# EasyEDA.net
KiCad netlist of a schematic drawn in EasyEDA Pro
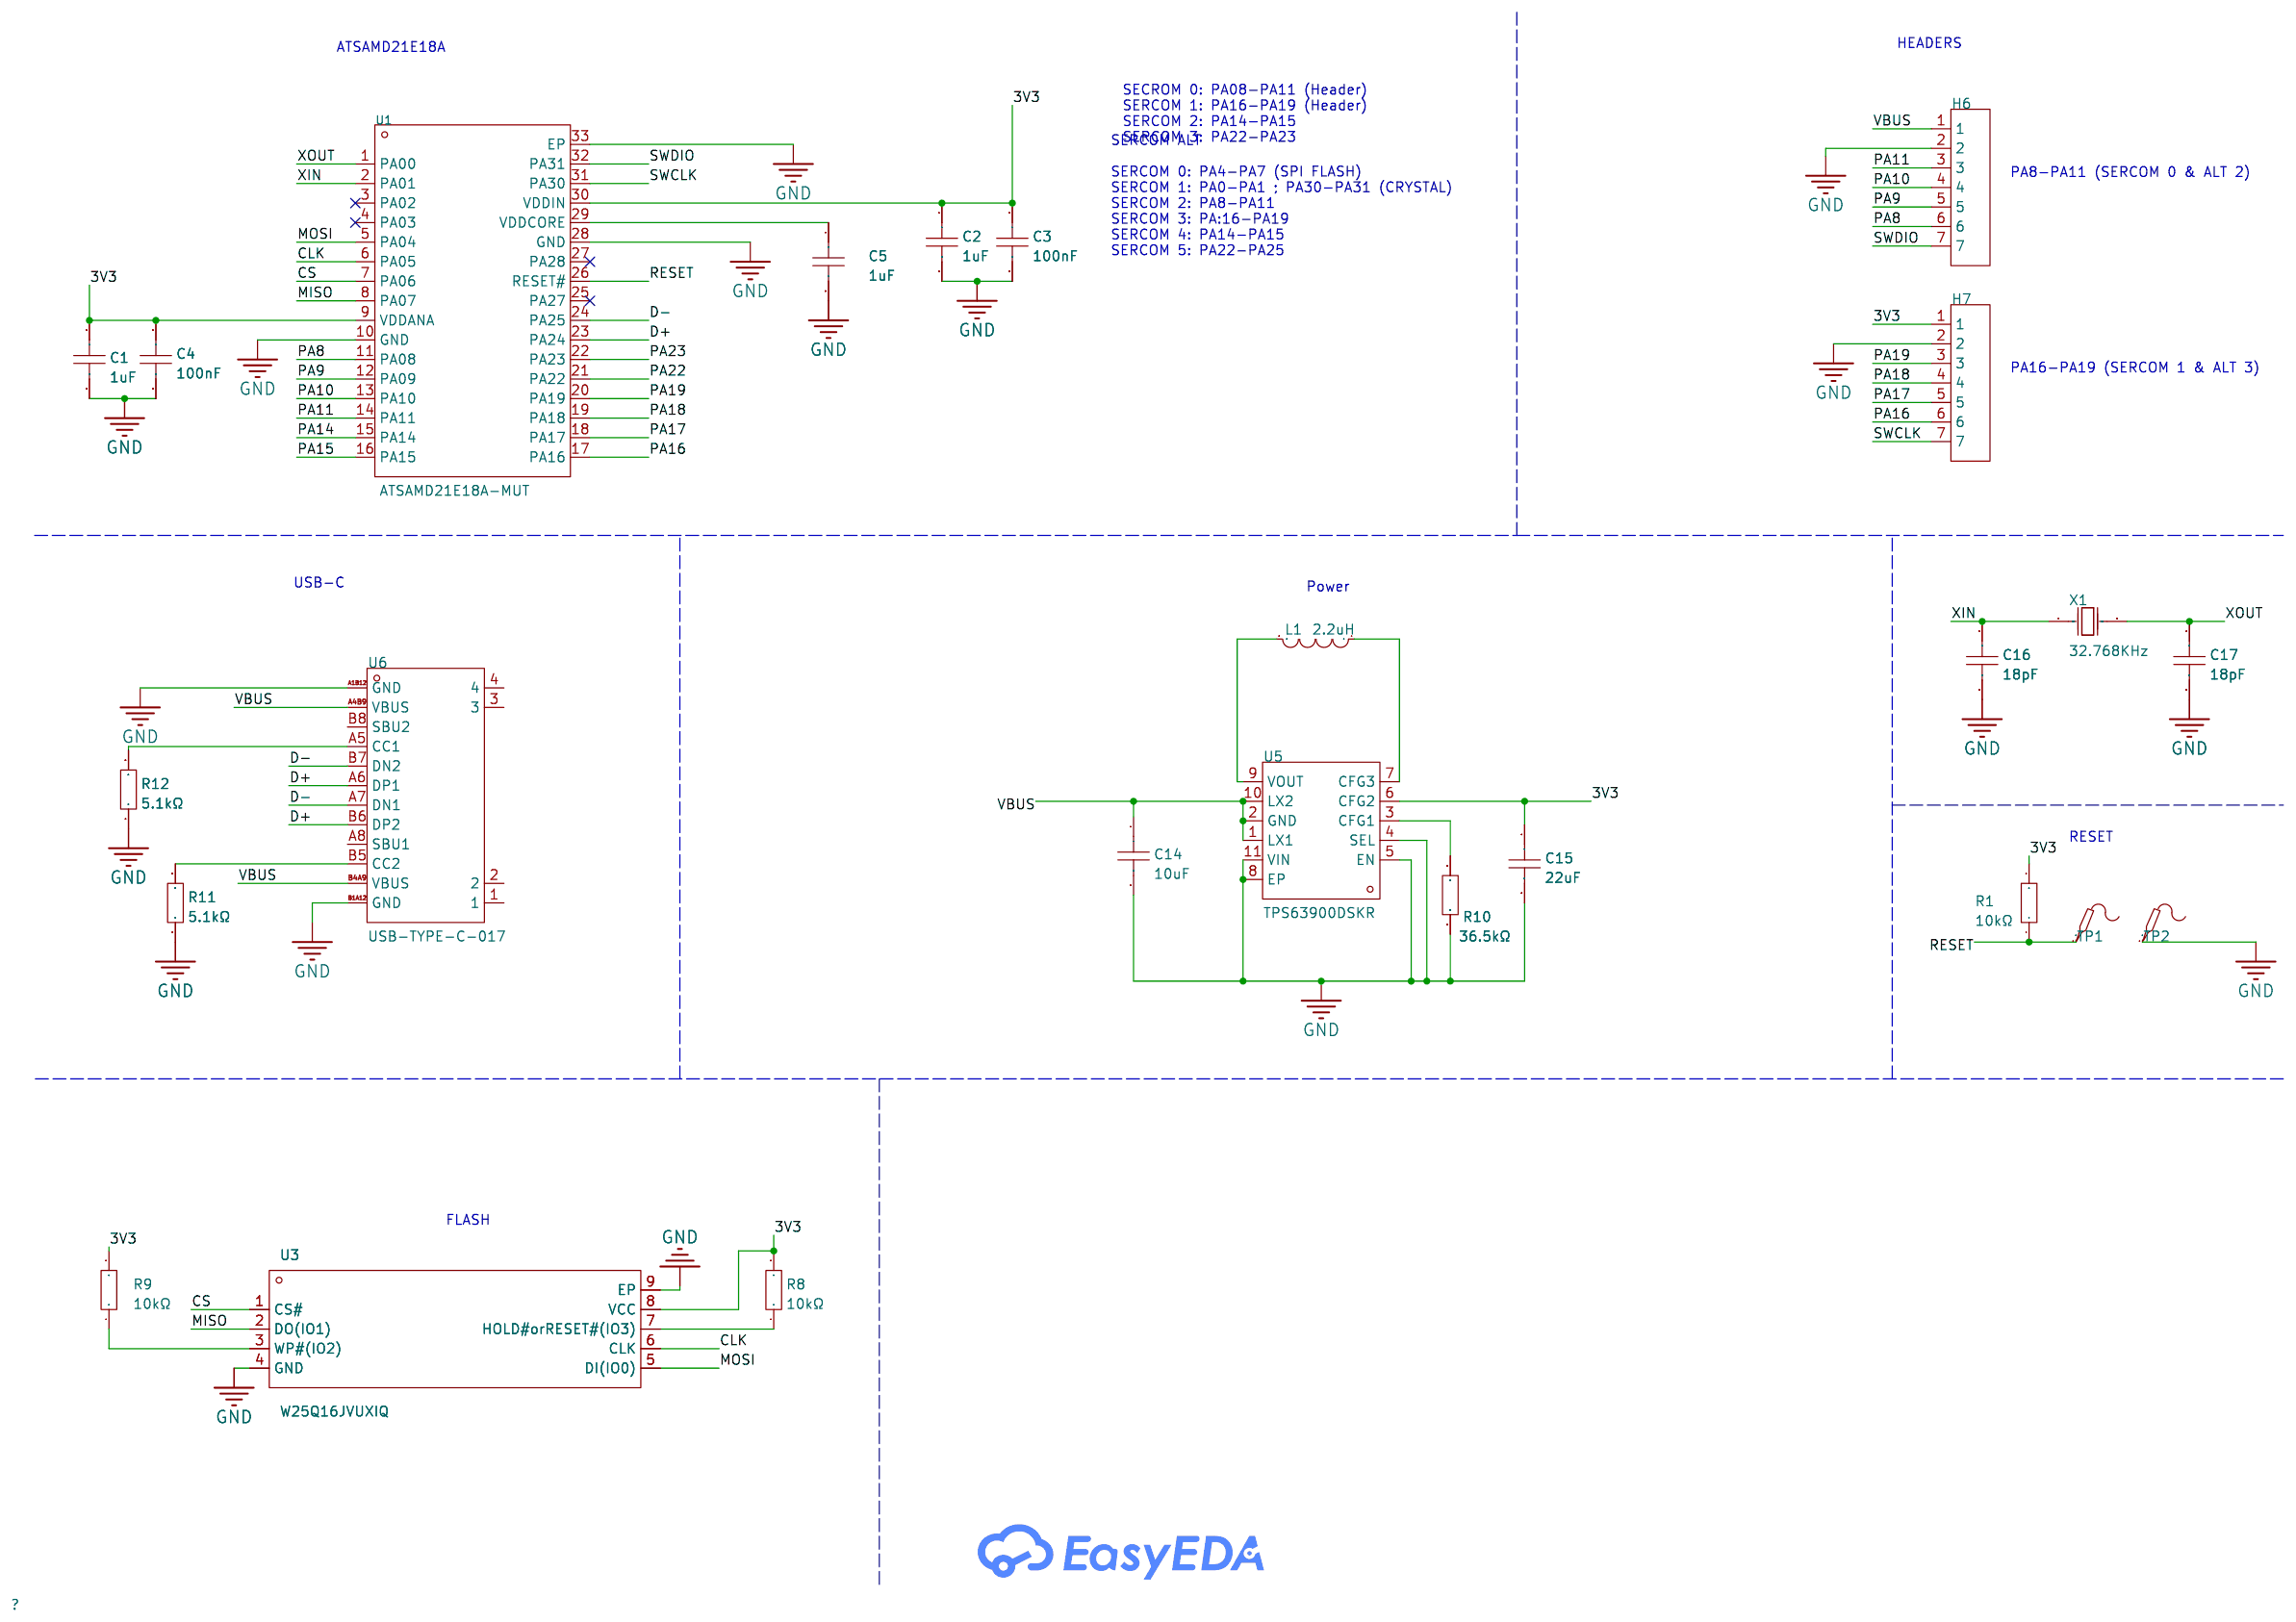
[diagram p0: schematic sheet]

(export (version "E")
  (design (tool "Eeschema 10.0.6"))
  (components
    (comp (ref "C1")
      (value "1uF")
      (footprint "easyedapro:C0402")
      (fields
        (field (name "Manufacturer Part") "CL05A105KA5NQNC")
        (field (name "Manufacturer") "SAMSUNG(三星)")
      )
      (libsource (lib "easyedapro") (part "CAP"))
    )
    (comp (ref "C2")
      (value "1uF")
      (footprint "easyedapro:C0402")
      (fields
        (field (name "Manufacturer Part") "CL05A105KA5NQNC")
        (field (name "Manufacturer") "SAMSUNG(三星)")
      )
      (libsource (lib "easyedapro") (part "CAP"))
    )
    (comp (ref "C3")
      (value "100nF")
      (footprint "easyedapro:C0402")
      (fields
        (field (name "Manufacturer Part") "CL05B104KO5NNNC")
        (field (name "Manufacturer") "SAMSUNG(三星)")
      )
      (libsource (lib "easyedapro") (part "CAP"))
    )
    (comp (ref "C4")
      (value "100nF")
      (footprint "easyedapro:C0402")
      (fields
        (field (name "Manufacturer Part") "CL05B104KO5NNNC")
        (field (name "Manufacturer") "SAMSUNG(三星)")
      )
      (libsource (lib "easyedapro") (part "CAP"))
    )
    (comp (ref "C5")
      (value "1uF")
      (footprint "easyedapro:C0402")
      (fields
        (field (name "Manufacturer Part") "CL05A105KA5NQNC")
        (field (name "Manufacturer") "SAMSUNG(三星)")
      )
      (libsource (lib "easyedapro") (part "CAP"))
    )
    (comp (ref "C14")
      (value "10uF")
      (footprint "easyedapro:C0402")
      (fields
        (field (name "Manufacturer Part") "CL05A106MQ5NUNC")
        (field (name "Manufacturer") "SAMSUNG(三星)")
      )
      (libsource (lib "easyedapro") (part "CAP"))
    )
    (comp (ref "C15")
      (value "22uF")
      (footprint "easyedapro:C0402")
      (fields
        (field (name "Manufacturer Part") "CL21A226MAQNNNE")
        (field (name "Manufacturer") "SAMSUNG(三星)")
      )
      (libsource (lib "easyedapro") (part "CAP"))
    )
    (comp (ref "C16")
      (value "18pF")
      (footprint "easyedapro:C0402")
      (libsource (lib "easyedapro") (part "CAP"))
    )
    (comp (ref "C17")
      (value "18pF")
      (footprint "easyedapro:C0402")
      (libsource (lib "easyedapro") (part "CAP"))
    )
    (comp (ref "H6")
      (value "~")
      (footprint "easyedapro:HDR-TH_7P-P2.54-V-M")
      (libsource (lib "easyedapro") (part "PZ254V-11-07P"))
    )
    (comp (ref "H7")
      (value "~")
      (footprint "easyedapro:HDR-TH_7P-P2.54-V-M")
      (libsource (lib "easyedapro") (part "PZ254V-11-07P"))
    )
    (comp (ref "L1")
      (value "2.2uH")
      (footprint "easyedapro:L0402")
      (fields (field (name "Manufacturer Part") "CY43-2.2UH") (field (name "Manufacturer") "SHOU HAN(首韩)"))
      (libsource (lib "easyedapro") (part "电感"))
    )
    (comp (ref "R1")
      (value "10kΩ")
      (footprint "easyedapro:R0603")
      (fields
        (field (name "Manufacturer Part") "0402WGF1002TCE")
        (field (name "Manufacturer") "UNI-ROYAL(厚声)")
      )
      (libsource (lib "easyedapro") (part "Res"))
    )
    (comp (ref "R8")
      (value "10kΩ")
      (footprint "easyedapro:R0603")
      (fields
        (field (name "Manufacturer Part") "0402WGF1002TCE")
        (field (name "Manufacturer") "UNI-ROYAL(厚声)")
      )
      (libsource (lib "easyedapro") (part "Res"))
    )
    (comp (ref "R9")
      (value "10kΩ")
      (footprint "easyedapro:R0603")
      (fields
        (field (name "Manufacturer Part") "0402WGF1002TCE")
        (field (name "Manufacturer") "UNI-ROYAL(厚声)")
      )
      (libsource (lib "easyedapro") (part "Res"))
    )
    (comp (ref "R10")
      (value "36.5kΩ")
      (footprint "easyedapro:R0603")
      (fields (field (name "Manufacturer Part") "AC0402FR-0736K5L") (field (name "Manufacturer") "YAGEO(国巨)"))
      (libsource (lib "easyedapro") (part "Res"))
    )
    (comp (ref "R11")
      (value "5.1kΩ")
      (footprint "easyedapro:R0603")
      (fields
        (field (name "Manufacturer Part") "0402WGF5101TCE")
        (field (name "Manufacturer") "UNI-ROYAL(厚声)")
      )
      (libsource (lib "easyedapro") (part "Res"))
    )
    (comp (ref "R12")
      (value "5.1kΩ")
      (footprint "easyedapro:R0603")
      (fields
        (field (name "Manufacturer Part") "0402WGF5101TCE")
        (field (name "Manufacturer") "UNI-ROYAL(厚声)")
      )
      (libsource (lib "easyedapro") (part "Res"))
    )
    (comp (ref "TP1")
      (value "~")
      (footprint "easyedapro:Test-Point-0.5mm")
      (description "Test Point 测试点")
      (libsource (lib "easyedapro") (part "Test-Point"))
    )
    (comp (ref "TP2")
      (value "~")
      (footprint "easyedapro:Test-Point-0.5mm")
      (description "Test Point 测试点")
      (libsource (lib "easyedapro") (part "Test-Point"))
    )
    (comp (ref "U1")
      (value "ATSAMD21E18A-MUT")
      (footprint "easyedapro:QFN-32_L5.0-W5.0-P0.50-TL-EP3.6")
      (fields (field (name "Manufacturer") "MICROCHIP(美国微芯)"))
      (libsource (lib "easyedapro") (part "ATSAMD21E18A-MUT_C2052801"))
    )
    (comp (ref "U3")
      (value "W25Q16JVUXIQ")
      (footprint "easyedapro:USON-8_L3.0-W2.0-P0.50-BL-EP")
      (fields (field (name "Manufacturer") "WINBOND(华邦)"))
      (libsource (lib "easyedapro") (part "W25Q16JVUXIQ"))
    )
    (comp (ref "U5")
      (value "TPS63900DSKR")
      (footprint "easyedapro:WSON-10_L2.5-W2.5-W0.50-TL-EP")
      (fields (field (name "Manufacturer") "TI(德州仪器)"))
      (libsource (lib "easyedapro") (part "TPS63900DSKR"))
    )
    (comp (ref "U6")
      (value "USB-TYPE-C-017")
      (footprint "easyedapro:USB-TYPE-C-SMD_C9900008089")
      (fields (field (name "Manufacturer") "DEALON(德艺隆)"))
      (libsource (lib "easyedapro") (part "USB-TYPE-C-017"))
    )
    (comp (ref "X1")
      (value "32.768KHz")
      (footprint "easyedapro:OSC-SMD_L3.2-W1.5")
      (fields (field (name "Manufacturer Part") "FC-135R") (field (name "Manufacturer") "EPSON"))
      (libsource (lib "easyedapro") (part "32.768KHz"))
    )
  )
  (nets
    (net (code "1") (name "/3V3") (class "Default")
      (node (ref "C1") (pin "1") (pinfunction "1_1") (pintype "input"))
      (node (ref "C15") (pin "1") (pinfunction "1_1") (pintype "input"))
      (node (ref "C2") (pin "1") (pinfunction "1_1") (pintype "input"))
      (node (ref "C3") (pin "1") (pinfunction "1_1") (pintype "input"))
      (node (ref "C4") (pin "1") (pinfunction "1_1") (pintype "input"))
      (node (ref "H7") (pin "1") (pinfunction "1_1") (pintype "unspecified"))
      (node (ref "R1") (pin "2") (pinfunction "2_2") (pintype "input"))
      (node (ref "R8") (pin "2") (pinfunction "2_2") (pintype "input"))
      (node (ref "R9") (pin "2") (pinfunction "2_2") (pintype "input"))
      (node (ref "U1") (pin "30") (pinfunction "VDDIN_30") (pintype "input"))
      (node (ref "U1") (pin "9") (pinfunction "VDDANA_9") (pintype "input"))
      (node (ref "U3") (pin "8") (pinfunction "VCC_8") (pintype "unspecified"))
      (node (ref "U5") (pin "6") (pinfunction "CFG2_6") (pintype "unspecified"))
    )
    (net (code "2") (name "/CLK") (class "Default")
      (node (ref "U1") (pin "6") (pinfunction "PA05_6") (pintype "input"))
      (node (ref "U3") (pin "6") (pinfunction "CLK_6") (pintype "unspecified"))
    )
    (net (code "3") (name "/CS") (class "Default")
      (node (ref "U1") (pin "7") (pinfunction "PA06_7") (pintype "input"))
      (node (ref "U3") (pin "1") (pinfunction "CS#_1") (pintype "unspecified"))
    )
    (net (code "4") (name "/D+") (class "Default")
      (node (ref "U1") (pin "23") (pinfunction "PA24_23") (pintype "input"))
      (node (ref "U6") (pin "A6") (pinfunction "DP1_A6") (pintype "unspecified"))
      (node (ref "U6") (pin "B6") (pinfunction "DP2_B6") (pintype "unspecified"))
    )
    (net (code "5") (name "/D-") (class "Default")
      (node (ref "U1") (pin "24") (pinfunction "PA25_24") (pintype "input"))
      (node (ref "U6") (pin "A7") (pinfunction "DN1_A7") (pintype "unspecified"))
      (node (ref "U6") (pin "B7") (pinfunction "DN2_B7") (pintype "unspecified"))
    )
    (net (code "6") (name "/MISO") (class "Default")
      (node (ref "U1") (pin "8") (pinfunction "PA07_8") (pintype "input"))
      (node (ref "U3") (pin "2") (pinfunction "DO(IO1)_2") (pintype "unspecified"))
    )
    (net (code "7") (name "/MOSI") (class "Default")
      (node (ref "U1") (pin "5") (pinfunction "PA04_5") (pintype "input"))
      (node (ref "U3") (pin "5") (pinfunction "DI(IO0)_5") (pintype "unspecified"))
    )
    (net (code "8") (name "/PA8") (class "Default")
      (node (ref "H6") (pin "6") (pinfunction "6_6") (pintype "unspecified"))
      (node (ref "U1") (pin "11") (pinfunction "PA08_11") (pintype "input"))
    )
    (net (code "9") (name "/PA9") (class "Default")
      (node (ref "H6") (pin "5") (pinfunction "5_5") (pintype "unspecified"))
      (node (ref "U1") (pin "12") (pinfunction "PA09_12") (pintype "input"))
    )
    (net (code "10") (name "/PA10") (class "Default")
      (node (ref "H6") (pin "4") (pinfunction "4_4") (pintype "unspecified"))
      (node (ref "U1") (pin "13") (pinfunction "PA10_13") (pintype "input"))
    )
    (net (code "11") (name "/PA11") (class "Default")
      (node (ref "H6") (pin "3") (pinfunction "3_3") (pintype "unspecified"))
      (node (ref "U1") (pin "14") (pinfunction "PA11_14") (pintype "input"))
    )
    (net (code "12") (name "/PA14") (class "Default")
      (node (ref "U1") (pin "15") (pinfunction "PA14_15") (pintype "input"))
    )
    (net (code "13") (name "/PA15") (class "Default")
      (node (ref "U1") (pin "16") (pinfunction "PA15_16") (pintype "input"))
    )
    (net (code "14") (name "/PA16") (class "Default")
      (node (ref "H7") (pin "6") (pinfunction "6_6") (pintype "unspecified"))
      (node (ref "U1") (pin "17") (pinfunction "PA16_17") (pintype "input"))
    )
    (net (code "15") (name "/PA17") (class "Default")
      (node (ref "H7") (pin "5") (pinfunction "5_5") (pintype "unspecified"))
      (node (ref "U1") (pin "18") (pinfunction "PA17_18") (pintype "input"))
    )
    (net (code "16") (name "/PA18") (class "Default")
      (node (ref "H7") (pin "4") (pinfunction "4_4") (pintype "unspecified"))
      (node (ref "U1") (pin "19") (pinfunction "PA18_19") (pintype "input"))
    )
    (net (code "17") (name "/PA19") (class "Default")
      (node (ref "H7") (pin "3") (pinfunction "3_3") (pintype "unspecified"))
      (node (ref "U1") (pin "20") (pinfunction "PA19_20") (pintype "input"))
    )
    (net (code "18") (name "/PA22") (class "Default")
      (node (ref "U1") (pin "21") (pinfunction "PA22_21") (pintype "input"))
    )
    (net (code "19") (name "/PA23") (class "Default")
      (node (ref "U1") (pin "22") (pinfunction "PA23_22") (pintype "input"))
    )
    (net (code "20") (name "/RESET") (class "Default")
      (node (ref "R1") (pin "1") (pinfunction "1_1") (pintype "input"))
      (node (ref "TP1") (pin "1") (pinfunction "1_1") (pintype "unspecified"))
      (node (ref "U1") (pin "26") (pinfunction "RESET#_26") (pintype "input"))
    )
    (net (code "21") (name "/SWCLK") (class "Default")
      (node (ref "H7") (pin "7") (pinfunction "7_7") (pintype "unspecified"))
      (node (ref "U1") (pin "31") (pinfunction "PA30_31") (pintype "input"))
    )
    (net (code "22") (name "/SWDIO") (class "Default")
      (node (ref "H6") (pin "7") (pinfunction "7_7") (pintype "unspecified"))
      (node (ref "U1") (pin "32") (pinfunction "PA31_32") (pintype "input"))
    )
    (net (code "23") (name "/VBUS") (class "Default")
      (node (ref "C14") (pin "1") (pinfunction "1_1") (pintype "input"))
      (node (ref "H6") (pin "1") (pinfunction "1_1") (pintype "unspecified"))
      (node (ref "U5") (pin "1") (pinfunction "LX1_1") (pintype "unspecified"))
      (node (ref "U5") (pin "10") (pinfunction "LX2_10") (pintype "unspecified"))
      (node (ref "U5") (pin "2") (pinfunction "GND_2") (pintype "unspecified"))
      (node (ref "U6") (pin "A4B9") (pinfunction "VBUS_A4B9") (pintype "unspecified"))
      (node (ref "U6") (pin "B4A9") (pinfunction "VBUS_B4A9") (pintype "unspecified"))
    )
    (net (code "24") (name "/XIN") (class "Default")
      (node (ref "C16") (pin "1") (pinfunction "1_1") (pintype "input"))
      (node (ref "U1") (pin "2") (pinfunction "PA01_2") (pintype "input"))
      (node (ref "X1") (pin "1") (pinfunction "OSC1_1") (pintype "input"))
    )
    (net (code "25") (name "/XOUT") (class "Default")
      (node (ref "C17") (pin "1") (pinfunction "1_1") (pintype "input"))
      (node (ref "U1") (pin "1") (pinfunction "PA00_1") (pintype "input"))
      (node (ref "X1") (pin "2") (pinfunction "OSC2_2") (pintype "input"))
    )
    (net (code "26") (name "GND") (class "Default")
      (node (ref "C1") (pin "2") (pinfunction "2_2") (pintype "input"))
      (node (ref "C14") (pin "2") (pinfunction "2_2") (pintype "input"))
      (node (ref "C15") (pin "2") (pinfunction "2_2") (pintype "input"))
      (node (ref "C16") (pin "2") (pinfunction "2_2") (pintype "input"))
      (node (ref "C17") (pin "2") (pinfunction "2_2") (pintype "input"))
      (node (ref "C2") (pin "2") (pinfunction "2_2") (pintype "input"))
      (node (ref "C3") (pin "2") (pinfunction "2_2") (pintype "input"))
      (node (ref "C4") (pin "2") (pinfunction "2_2") (pintype "input"))
      (node (ref "C5") (pin "2") (pinfunction "2_2") (pintype "input"))
      (node (ref "H6") (pin "2") (pinfunction "2_2") (pintype "unspecified"))
      (node (ref "H7") (pin "2") (pinfunction "2_2") (pintype "unspecified"))
      (node (ref "R10") (pin "2") (pinfunction "2_2") (pintype "input"))
      (node (ref "R11") (pin "1") (pinfunction "1_1") (pintype "input"))
      (node (ref "R12") (pin "1") (pinfunction "1_1") (pintype "input"))
      (node (ref "TP2") (pin "1") (pinfunction "1_1") (pintype "unspecified"))
      (node (ref "U1") (pin "10") (pinfunction "GND_10") (pintype "input"))
      (node (ref "U1") (pin "28") (pinfunction "GND_28") (pintype "input"))
      (node (ref "U1") (pin "33") (pinfunction "EP_33") (pintype "input"))
      (node (ref "U3") (pin "4") (pinfunction "GND_4") (pintype "unspecified"))
      (node (ref "U3") (pin "9") (pinfunction "EP_9") (pintype "unspecified"))
      (node (ref "U5") (pin "11") (pinfunction "VIN_11") (pintype "unspecified"))
      (node (ref "U5") (pin "4") (pinfunction "SEL_4") (pintype "unspecified"))
      (node (ref "U5") (pin "5") (pinfunction "EN_5") (pintype "unspecified"))
      (node (ref "U5") (pin "8") (pinfunction "EP_8") (pintype "unspecified"))
      (node (ref "U6") (pin "A1B12") (pinfunction "GND_A1B12") (pintype "unspecified"))
      (node (ref "U6") (pin "B1A12") (pinfunction "GND_B1A12") (pintype "unspecified"))
    )
    (net (code "27") (name "Net-(U1-VDDCORE)") (class "Default")
      (node (ref "C5") (pin "1") (pinfunction "1_1") (pintype "input"))
      (node (ref "U1") (pin "29") (pinfunction "VDDCORE_29") (pintype "input"))
    )
    (net (code "28") (name "Net-(U3-HOLD#orRESET#(IO3))") (class "Default")
      (node (ref "R8") (pin "1") (pinfunction "1_1") (pintype "input"))
      (node (ref "U3") (pin "7") (pinfunction "HOLD#orRESET#(IO3)_7") (pintype "unspecified"))
    )
    (net (code "29") (name "Net-(U3-WP#(IO2))") (class "Default")
      (node (ref "R9") (pin "1") (pinfunction "1_1") (pintype "input"))
      (node (ref "U3") (pin "3") (pinfunction "WP#(IO2)_3") (pintype "unspecified"))
    )
    (net (code "30") (name "Net-(U5-CFG1)") (class "Default")
      (node (ref "R10") (pin "1") (pinfunction "1_1") (pintype "input"))
      (node (ref "U5") (pin "3") (pinfunction "CFG1_3") (pintype "unspecified"))
    )
    (net (code "31") (name "Net-(U5-CFG3)") (class "Default")
      (node (ref "L1") (pin "1") (pinfunction "1_1") (pintype "input"))
      (node (ref "U5") (pin "7") (pinfunction "CFG3_7") (pintype "unspecified"))
    )
    (net (code "32") (name "Net-(U5-VOUT)") (class "Default")
      (node (ref "L1") (pin "2") (pinfunction "2_2") (pintype "input"))
      (node (ref "U5") (pin "9") (pinfunction "VOUT_9") (pintype "unspecified"))
    )
    (net (code "33") (name "Net-(U6-CC1)") (class "Default")
      (node (ref "R12") (pin "2") (pinfunction "2_2") (pintype "input"))
      (node (ref "U6") (pin "A5") (pinfunction "CC1_A5") (pintype "unspecified"))
    )
    (net (code "34") (name "Net-(U6-CC2)") (class "Default")
      (node (ref "R11") (pin "2") (pinfunction "2_2") (pintype "input"))
      (node (ref "U6") (pin "B5") (pinfunction "CC2_B5") (pintype "unspecified"))
    )
    (net (code "35") (name "unconnected-(U1-PA02-Pad3)") (class "Default")
      (node (ref "U1") (pin "3") (pinfunction "PA02_3") (pintype "input+no_connect"))
    )
    (net (code "36") (name "unconnected-(U1-PA03-Pad4)") (class "Default")
      (node (ref "U1") (pin "4") (pinfunction "PA03_4") (pintype "input+no_connect"))
    )
    (net (code "37") (name "unconnected-(U1-PA27-Pad25)") (class "Default")
      (node (ref "U1") (pin "25") (pinfunction "PA27_25") (pintype "input+no_connect"))
    )
    (net (code "38") (name "unconnected-(U1-PA28-Pad27)") (class "Default")
      (node (ref "U1") (pin "27") (pinfunction "PA28_27") (pintype "input+no_connect"))
    )
    (net (code "39") (name "unconnected-(U6-Pad1)") (class "Default")
      (node (ref "U6") (pin "1") (pinfunction "1_1") (pintype "unspecified"))
    )
    (net (code "40") (name "unconnected-(U6-Pad2)") (class "Default")
      (node (ref "U6") (pin "2") (pinfunction "2_2") (pintype "unspecified"))
    )
    (net (code "41") (name "unconnected-(U6-Pad3)") (class "Default")
      (node (ref "U6") (pin "3") (pinfunction "3_3") (pintype "unspecified"))
    )
    (net (code "42") (name "unconnected-(U6-Pad4)") (class "Default")
      (node (ref "U6") (pin "4") (pinfunction "4_4") (pintype "unspecified"))
    )
    (net (code "43") (name "unconnected-(U6-SBU1-PadA8)") (class "Default")
      (node (ref "U6") (pin "A8") (pinfunction "SBU1_A8") (pintype "unspecified"))
    )
    (net (code "44") (name "unconnected-(U6-SBU2-PadB8)") (class "Default")
      (node (ref "U6") (pin "B8") (pinfunction "SBU2_B8") (pintype "unspecified"))
    )
  )
)
